# 13_-_CONNECTOR.net
KiCad netlist of a schematic drawn in Altium Designer
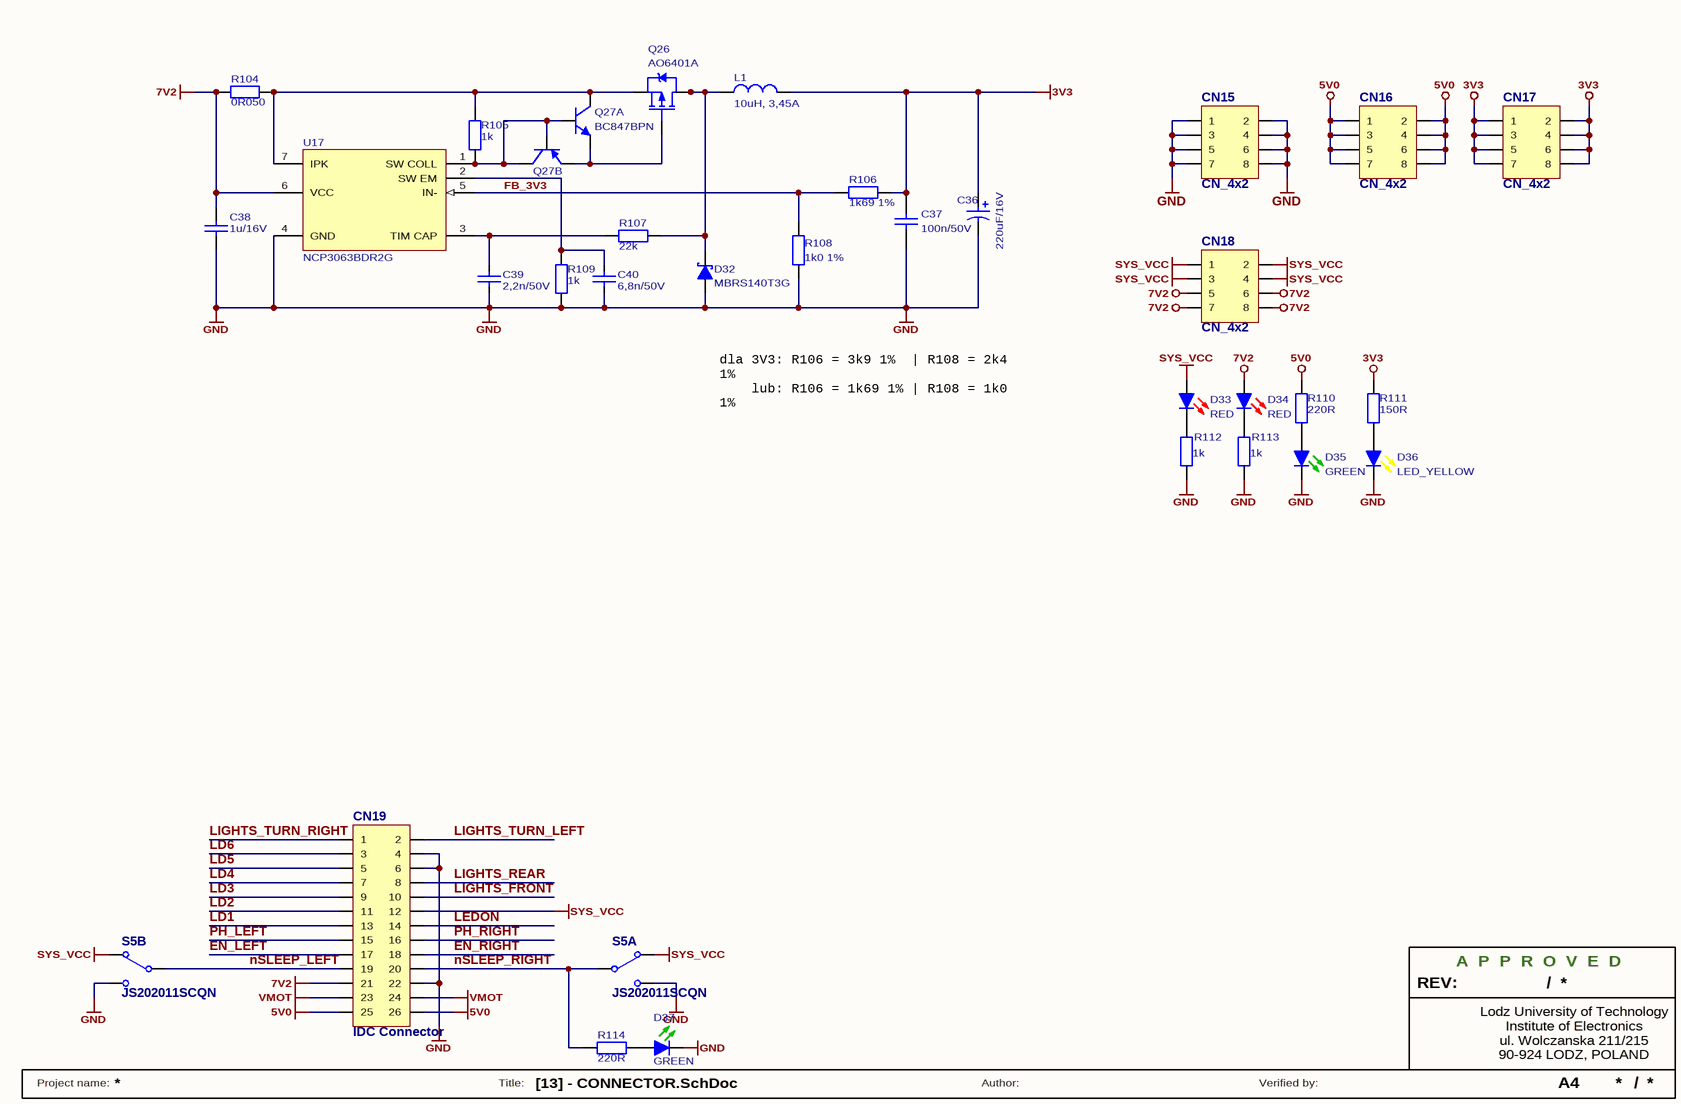
[diagram p0: [13] - CONNECTOR.SchDoc]

(export (version "E")
  (design (tool "Eeschema 10.0.6"))
  (components
    (comp (ref "C36")
      (value "220uF/16V")
      (footprint "CES_E_8.3x8.3_6.2")
      (description "Polarized Capacitor")
      (libsource (lib "capacitors") (part "Cap Pol"))
    )
    (comp (ref "C37")
      (value "100n/50V")
      (footprint "C0805")
      (description "Capacitor")
      (libsource (lib "capacitors") (part "Cap"))
    )
    (comp (ref "C38")
      (value "1u/16V")
      (footprint "C0805")
      (description "Capacitor")
      (libsource (lib "") (part "Cap_1"))
    )
    (comp (ref "C39")
      (value "2,2n/50V")
      (footprint "C0805")
      (description "Capacitor")
      (libsource (lib "") (part "Cap_2"))
    )
    (comp (ref "C40")
      (value "6,8n/50V")
      (footprint "C0805")
      (description "Capacitor")
      (libsource (lib "") (part "Cap_2"))
    )
    (comp (ref "CN15") (value "CN_4x2") (footprint "GP_4x2") (libsource (lib "goldpin_male") (part "CN_4x2")))
    (comp (ref "CN16") (value "CN_4x2") (footprint "GP_4x2") (libsource (lib "goldpin_male") (part "CN_4x2")))
    (comp (ref "CN17") (value "CN_4x2") (footprint "GP_4x2") (libsource (lib "goldpin_male") (part "CN_4x2")))
    (comp (ref "CN18") (value "CN_4x2") (footprint "GP_4x2") (libsource (lib "goldpin_male") (part "CN_4x2")))
    (comp (ref "CN19")
      (value "IDC Connector")
      (footprint "IDC26_RA_LONG_W_CN")
      (libsource (lib "idc") (part "CN_13x2"))
    )
    (comp (ref "D32")
      (value "MBRS140T3G")
      (footprint "SMB")
      (description "Schottky barrier rectifier: 40V, 1A")
      (libsource (lib "diodes_schottky") (part "MBRS140T3G"))
    )
    (comp (ref "D33")
      (value "RED")
      (footprint "LED0805R")
      (description "RED LED")
      (libsource (lib "leds") (part "LED_RED"))
    )
    (comp (ref "D34")
      (value "RED")
      (footprint "LED0805R")
      (description "RED LED")
      (libsource (lib "leds") (part "LED_RED"))
    )
    (comp (ref "D35")
      (value "GREEN")
      (footprint "LED0805G")
      (description "GREEN LED")
      (libsource (lib "leds") (part "LED_GREEN"))
    )
    (comp (ref "D36")
      (value "LED_YELLOW")
      (footprint "LED0805Y")
      (description "YELLOW LED")
      (libsource (lib "leds") (part "LED_YELLOW"))
    )
    (comp (ref "D37")
      (value "GREEN")
      (footprint "LED0805G")
      (description "GREEN LED")
      (libsource (lib "leds") (part "LED_GREEN"))
    )
    (comp (ref "L1")
      (value "10uH, 3,45A")
      (footprint "PSDB1005")
      (description "10uH, 20%, 3,45A, PSDB1005N Series Inductor")
      (libsource (lib "inductors") (part "PSDB1005NT100"))
    )
    (comp (ref "Q26")
      (value "AO6401A")
      (footprint "SOT-23-6")
      (description "P-Channel MOSFET; -60V, -5A, 1.3W;")
      (libsource (lib "transistors_mos") (part "AO6401A"))
    )
    (comp (ref "Q27")
      (value "BC847BPN")
      (footprint "SOT-323-6 (SOT-363, SC88, SC70-6)")
      (description "PNP/NPN General Purpose Transistor (VCE=45V, IC=100mA)")
      (libsource (lib "transistors_bjt") (part "BC847BPN"))
    )
    (comp (ref "R104")
      (value "0R050")
      (footprint "R0805")
      (description "Resistor")
      (libsource (lib "") (part "Res_1"))
    )
    (comp (ref "R105")
      (value "1k")
      (footprint "R0805")
      (description "Resistor")
      (libsource (lib "resistors") (part "Res"))
    )
    (comp (ref "R106")
      (value "1k69 1%")
      (footprint "R0805")
      (description "Resistor")
      (libsource (lib "") (part "Res_1"))
    )
    (comp (ref "R107")
      (value "22k")
      (footprint "R0805")
      (description "Resistor")
      (libsource (lib "") (part "Res_2"))
    )
    (comp (ref "R108")
      (value "1k0 1%")
      (footprint "R0805")
      (description "Resistor")
      (libsource (lib "resistors") (part "Res"))
    )
    (comp (ref "R109")
      (value "1k")
      (footprint "R0805")
      (description "Resistor")
      (libsource (lib "resistors") (part "Res"))
    )
    (comp (ref "R110")
      (value "220R")
      (footprint "R0805")
      (description "Resistor")
      (libsource (lib "resistors") (part "Res"))
    )
    (comp (ref "R111")
      (value "150R")
      (footprint "R0805")
      (description "Resistor")
      (libsource (lib "resistors") (part "Res"))
    )
    (comp (ref "R112")
      (value "1k")
      (footprint "R0805")
      (description "Resistor")
      (libsource (lib "resistors") (part "Res"))
    )
    (comp (ref "R113")
      (value "1k")
      (footprint "R0805")
      (description "Resistor")
      (libsource (lib "resistors") (part "Res"))
    )
    (comp (ref "R114")
      (value "220R")
      (footprint "R0805")
      (description "Resistor")
      (libsource (lib "") (part "Res_1"))
    )
    (comp (ref "S5")
      (value "JS202011SCQN")
      (footprint "JS202011SCQN")
      (description "C&K JS202011SCQN DPDT Switch")
      (fields (field (name "PUBLISHER") "Altium Limited"))
      (libsource (lib "switches_slide") (part "JS202011SCQN"))
    )
    (comp (ref "U17")
      (value "NCP3063BDR2G")
      (footprint "SO8")
      (description "DC-DC Converter NCP3063BDR2G (Farnell 1547126)")
      (libsource (lib "switched_voltage_regulators") (part "NCP3063BDR2G"))
    )
  )
  (nets
    (net (code "1") (name "/EN_LEFT") (class "Default")
      (node (ref "CN19") (pin "17") (pinfunction "17_17") (pintype "passive"))
    )
    (net (code "2") (name "/EN_RIGHT") (class "Default")
      (node (ref "CN19") (pin "18") (pinfunction "18_18") (pintype "passive"))
    )
    (net (code "3") (name "/FB_3V3") (class "Default")
      (node (ref "R106") (pin "1") (pinfunction "1_1") (pintype "passive"))
      (node (ref "R108") (pin "1") (pinfunction "1_1") (pintype "passive"))
      (node (ref "U17") (pin "5") (pinfunction "IN-_5") (pintype "input"))
    )
    (net (code "4") (name "/LD1") (class "Default")
      (node (ref "CN19") (pin "13") (pinfunction "13_13") (pintype "passive"))
    )
    (net (code "5") (name "/LD2") (class "Default")
      (node (ref "CN19") (pin "11") (pinfunction "11_11") (pintype "passive"))
    )
    (net (code "6") (name "/LD3") (class "Default")
      (node (ref "CN19") (pin "9") (pinfunction "9_9") (pintype "passive"))
    )
    (net (code "7") (name "/LD4") (class "Default")
      (node (ref "CN19") (pin "7") (pinfunction "7_7") (pintype "passive"))
    )
    (net (code "8") (name "/LD5") (class "Default")
      (node (ref "CN19") (pin "5") (pinfunction "5_5") (pintype "passive"))
    )
    (net (code "9") (name "/LD6") (class "Default")
      (node (ref "CN19") (pin "3") (pinfunction "3_3") (pintype "passive"))
    )
    (net (code "10") (name "/LEDON") (class "Default")
      (node (ref "CN19") (pin "14") (pinfunction "14_14") (pintype "passive"))
    )
    (net (code "11") (name "/LIGHTS_FRONT") (class "Default")
      (node (ref "CN19") (pin "10") (pinfunction "10_10") (pintype "passive"))
    )
    (net (code "12") (name "/LIGHTS_REAR") (class "Default")
      (node (ref "CN19") (pin "8") (pinfunction "8_8") (pintype "passive"))
    )
    (net (code "13") (name "/LIGHTS_TURN_LEFT") (class "Default")
      (node (ref "CN19") (pin "2") (pinfunction "2_2") (pintype "passive"))
    )
    (net (code "14") (name "/LIGHTS_TURN_RIGHT") (class "Default")
      (node (ref "CN19") (pin "1") (pinfunction "1_1") (pintype "passive"))
    )
    (net (code "15") (name "/PH_LEFT") (class "Default")
      (node (ref "CN19") (pin "15") (pinfunction "15_15") (pintype "passive"))
    )
    (net (code "16") (name "/PH_RIGHT") (class "Default")
      (node (ref "CN19") (pin "16") (pinfunction "16_16") (pintype "passive"))
    )
    (net (code "17") (name "/nSLEEP_LEFT") (class "Default")
      (node (ref "CN19") (pin "19") (pinfunction "19_19") (pintype "passive"))
      (node (ref "S5") (pin "5") (pinfunction "COMMON2_5") (pintype "passive"))
    )
    (net (code "18") (name "/nSLEEP_RIGHT") (class "Default")
      (node (ref "CN19") (pin "20") (pinfunction "20_20") (pintype "passive"))
      (node (ref "R114") (pin "1") (pinfunction "1_1") (pintype "passive"))
      (node (ref "S5") (pin "1") (pinfunction "COMMON1_1") (pintype "passive"))
    )
    (net (code "19") (name "3V3") (class "Default")
      (node (ref "C36") (pin "1") (pinfunction "1_1") (pintype "passive"))
      (node (ref "C37") (pin "2") (pinfunction "2_2") (pintype "passive"))
      (node (ref "CN17") (pin "1") (pinfunction "1_1") (pintype "passive"))
      (node (ref "CN17") (pin "2") (pinfunction "2_2") (pintype "passive"))
      (node (ref "CN17") (pin "3") (pinfunction "3_3") (pintype "passive"))
      (node (ref "CN17") (pin "4") (pinfunction "4_4") (pintype "passive"))
      (node (ref "CN17") (pin "5") (pinfunction "5_5") (pintype "passive"))
      (node (ref "CN17") (pin "6") (pinfunction "6_6") (pintype "passive"))
      (node (ref "CN17") (pin "7") (pinfunction "7_7") (pintype "passive"))
      (node (ref "CN17") (pin "8") (pinfunction "8_8") (pintype "passive"))
      (node (ref "L1") (pin "2") (pinfunction "2_2") (pintype "passive"))
      (node (ref "R106") (pin "2") (pinfunction "2_2") (pintype "passive"))
      (node (ref "R111") (pin "1") (pinfunction "1_1") (pintype "passive"))
    )
    (net (code "20") (name "5V0") (class "Default")
      (node (ref "CN16") (pin "1") (pinfunction "1_1") (pintype "passive"))
      (node (ref "CN16") (pin "2") (pinfunction "2_2") (pintype "passive"))
      (node (ref "CN16") (pin "3") (pinfunction "3_3") (pintype "passive"))
      (node (ref "CN16") (pin "4") (pinfunction "4_4") (pintype "passive"))
      (node (ref "CN16") (pin "5") (pinfunction "5_5") (pintype "passive"))
      (node (ref "CN16") (pin "6") (pinfunction "6_6") (pintype "passive"))
      (node (ref "CN16") (pin "7") (pinfunction "7_7") (pintype "passive"))
      (node (ref "CN16") (pin "8") (pinfunction "8_8") (pintype "passive"))
      (node (ref "CN19") (pin "25") (pinfunction "25_25") (pintype "passive"))
      (node (ref "CN19") (pin "26") (pinfunction "26_26") (pintype "passive"))
      (node (ref "R110") (pin "1") (pinfunction "1_1") (pintype "passive"))
    )
    (net (code "21") (name "7V2") (class "Default")
      (node (ref "C38") (pin "2") (pinfunction "2_2") (pintype "passive"))
      (node (ref "CN18") (pin "5") (pinfunction "5_5") (pintype "passive"))
      (node (ref "CN18") (pin "6") (pinfunction "6_6") (pintype "passive"))
      (node (ref "CN18") (pin "7") (pinfunction "7_7") (pintype "passive"))
      (node (ref "CN18") (pin "8") (pinfunction "8_8") (pintype "passive"))
      (node (ref "CN19") (pin "21") (pinfunction "21_21") (pintype "passive"))
      (node (ref "D34") (pin "1") (pinfunction "A_1") (pintype "passive"))
      (node (ref "R104") (pin "1") (pinfunction "1_1") (pintype "passive"))
      (node (ref "U17") (pin "6") (pinfunction "VCC_6") (pintype "power_in"))
    )
    (net (code "22") (name "GND") (class "Default")
      (node (ref "C36") (pin "2") (pinfunction "2_2") (pintype "passive"))
      (node (ref "C37") (pin "1") (pinfunction "1_1") (pintype "passive"))
      (node (ref "C38") (pin "1") (pinfunction "1_1") (pintype "passive"))
      (node (ref "C39") (pin "1") (pinfunction "1_1") (pintype "passive"))
      (node (ref "C40") (pin "1") (pinfunction "1_1") (pintype "passive"))
      (node (ref "CN15") (pin "1") (pinfunction "1_1") (pintype "passive"))
      (node (ref "CN15") (pin "2") (pinfunction "2_2") (pintype "passive"))
      (node (ref "CN15") (pin "3") (pinfunction "3_3") (pintype "passive"))
      (node (ref "CN15") (pin "4") (pinfunction "4_4") (pintype "passive"))
      (node (ref "CN15") (pin "5") (pinfunction "5_5") (pintype "passive"))
      (node (ref "CN15") (pin "6") (pinfunction "6_6") (pintype "passive"))
      (node (ref "CN15") (pin "7") (pinfunction "7_7") (pintype "passive"))
      (node (ref "CN15") (pin "8") (pinfunction "8_8") (pintype "passive"))
      (node (ref "CN19") (pin "22") (pinfunction "22_22") (pintype "passive"))
      (node (ref "CN19") (pin "4") (pinfunction "4_4") (pintype "passive"))
      (node (ref "CN19") (pin "6") (pinfunction "6_6") (pintype "passive"))
      (node (ref "D32") (pin "1") (pinfunction "A_1") (pintype "passive"))
      (node (ref "D35") (pin "2") (pinfunction "K_2") (pintype "passive"))
      (node (ref "D36") (pin "2") (pinfunction "K_2") (pintype "passive"))
      (node (ref "D37") (pin "2") (pinfunction "K_2") (pintype "passive"))
      (node (ref "R108") (pin "2") (pinfunction "2_2") (pintype "passive"))
      (node (ref "R109") (pin "2") (pinfunction "2_2") (pintype "passive"))
      (node (ref "R112") (pin "2") (pinfunction "2_2") (pintype "passive"))
      (node (ref "R113") (pin "2") (pinfunction "2_2") (pintype "passive"))
      (node (ref "S5") (pin "3") (pinfunction "NO1_3") (pintype "passive"))
      (node (ref "S5") (pin "6") (pinfunction "NO2_6") (pintype "passive"))
      (node (ref "U17") (pin "4") (pinfunction "GND_4") (pintype "power_in"))
    )
    (net (code "23") (name "Net-(D32-K)") (class "Default")
      (node (ref "D32") (pin "2") (pinfunction "K_2") (pintype "passive"))
      (node (ref "L1") (pin "1") (pinfunction "1_1") (pintype "passive"))
      (node (ref "Q26") (pin "1") (pinfunction "D_1") (pintype "passive"))
      (node (ref "Q26") (pin "2") (pinfunction "D_2") (pintype "passive"))
      (node (ref "Q26") (pin "5") (pinfunction "D_5") (pintype "passive"))
      (node (ref "Q26") (pin "6") (pinfunction "D_6") (pintype "passive"))
      (node (ref "R107") (pin "1") (pinfunction "1_1") (pintype "passive"))
    )
    (net (code "24") (name "Net-(D33-K)") (class "Default")
      (node (ref "D33") (pin "2") (pinfunction "K_2") (pintype "passive"))
      (node (ref "R112") (pin "1") (pinfunction "1_1") (pintype "passive"))
    )
    (net (code "25") (name "Net-(D34-K)") (class "Default")
      (node (ref "D34") (pin "2") (pinfunction "K_2") (pintype "passive"))
      (node (ref "R113") (pin "1") (pinfunction "1_1") (pintype "passive"))
    )
    (net (code "26") (name "Net-(D35-A)") (class "Default")
      (node (ref "D35") (pin "1") (pinfunction "A_1") (pintype "passive"))
      (node (ref "R110") (pin "2") (pinfunction "2_2") (pintype "passive"))
    )
    (net (code "27") (name "Net-(D36-A)") (class "Default")
      (node (ref "D36") (pin "1") (pinfunction "A_1") (pintype "passive"))
      (node (ref "R111") (pin "2") (pinfunction "2_2") (pintype "passive"))
    )
    (net (code "28") (name "Net-(D37-A)") (class "Default")
      (node (ref "D37") (pin "1") (pinfunction "A_1") (pintype "passive"))
      (node (ref "R114") (pin "2") (pinfunction "2_2") (pintype "passive"))
    )
    (net (code "29") (name "Net-(Q26-G)") (class "Default")
      (node (ref "Q26") (pin "3") (pinfunction "G_3") (pintype "passive"))
      (node (ref "Q27") (pin "1") (pinfunction "EA_1") (pintype "passive"))
      (node (ref "Q27") (pin "4") (pinfunction "EB_4") (pintype "passive"))
    )
    (net (code "30") (name "Net-(Q26-S)") (class "Default")
      (node (ref "Q26") (pin "4") (pinfunction "S_4") (pintype "passive"))
      (node (ref "Q27") (pin "6") (pinfunction "CA_6") (pintype "passive"))
      (node (ref "R104") (pin "2") (pinfunction "2_2") (pintype "passive"))
      (node (ref "R105") (pin "1") (pinfunction "1_1") (pintype "passive"))
      (node (ref "U17") (pin "7") (pinfunction "IPK_7") (pintype "passive"))
    )
    (net (code "31") (name "Net-(Q27A-BA)") (class "Default")
      (node (ref "Q27") (pin "2") (pinfunction "BA_2") (pintype "passive"))
      (node (ref "Q27") (pin "3") (pinfunction "CB_3") (pintype "passive"))
      (node (ref "Q27") (pin "5") (pinfunction "BB_5") (pintype "passive"))
      (node (ref "R105") (pin "2") (pinfunction "2_2") (pintype "passive"))
      (node (ref "U17") (pin "1") (pinfunction "SW_COLL_1") (pintype "passive"))
    )
    (net (code "32") (name "Net-(U17-SW_EM)") (class "Default")
      (node (ref "C40") (pin "2") (pinfunction "2_2") (pintype "passive"))
      (node (ref "R109") (pin "1") (pinfunction "1_1") (pintype "passive"))
      (node (ref "U17") (pin "2") (pinfunction "SW_EM_2") (pintype "passive"))
    )
    (net (code "33") (name "Net-(U17-TIM_CAP)") (class "Default")
      (node (ref "C39") (pin "2") (pinfunction "2_2") (pintype "passive"))
      (node (ref "R107") (pin "2") (pinfunction "2_2") (pintype "passive"))
      (node (ref "U17") (pin "3") (pinfunction "TIM_CAP_3") (pintype "passive"))
    )
    (net (code "34") (name "SYS_VCC") (class "Default")
      (node (ref "CN18") (pin "1") (pinfunction "1_1") (pintype "passive"))
      (node (ref "CN18") (pin "2") (pinfunction "2_2") (pintype "passive"))
      (node (ref "CN18") (pin "3") (pinfunction "3_3") (pintype "passive"))
      (node (ref "CN18") (pin "4") (pinfunction "4_4") (pintype "passive"))
      (node (ref "CN19") (pin "12") (pinfunction "12_12") (pintype "passive"))
      (node (ref "D33") (pin "1") (pinfunction "A_1") (pintype "passive"))
      (node (ref "S5") (pin "2") (pinfunction "NC1_2") (pintype "passive"))
      (node (ref "S5") (pin "4") (pinfunction "NC2_4") (pintype "passive"))
    )
    (net (code "35") (name "VMOT") (class "Default")
      (node (ref "CN19") (pin "23") (pinfunction "23_23") (pintype "passive"))
      (node (ref "CN19") (pin "24") (pinfunction "24_24") (pintype "passive"))
    )
  )
)
